# V2_0_2_Contactor_Switch.net
KiCad netlist of a schematic drawn in EasyEDA Pro
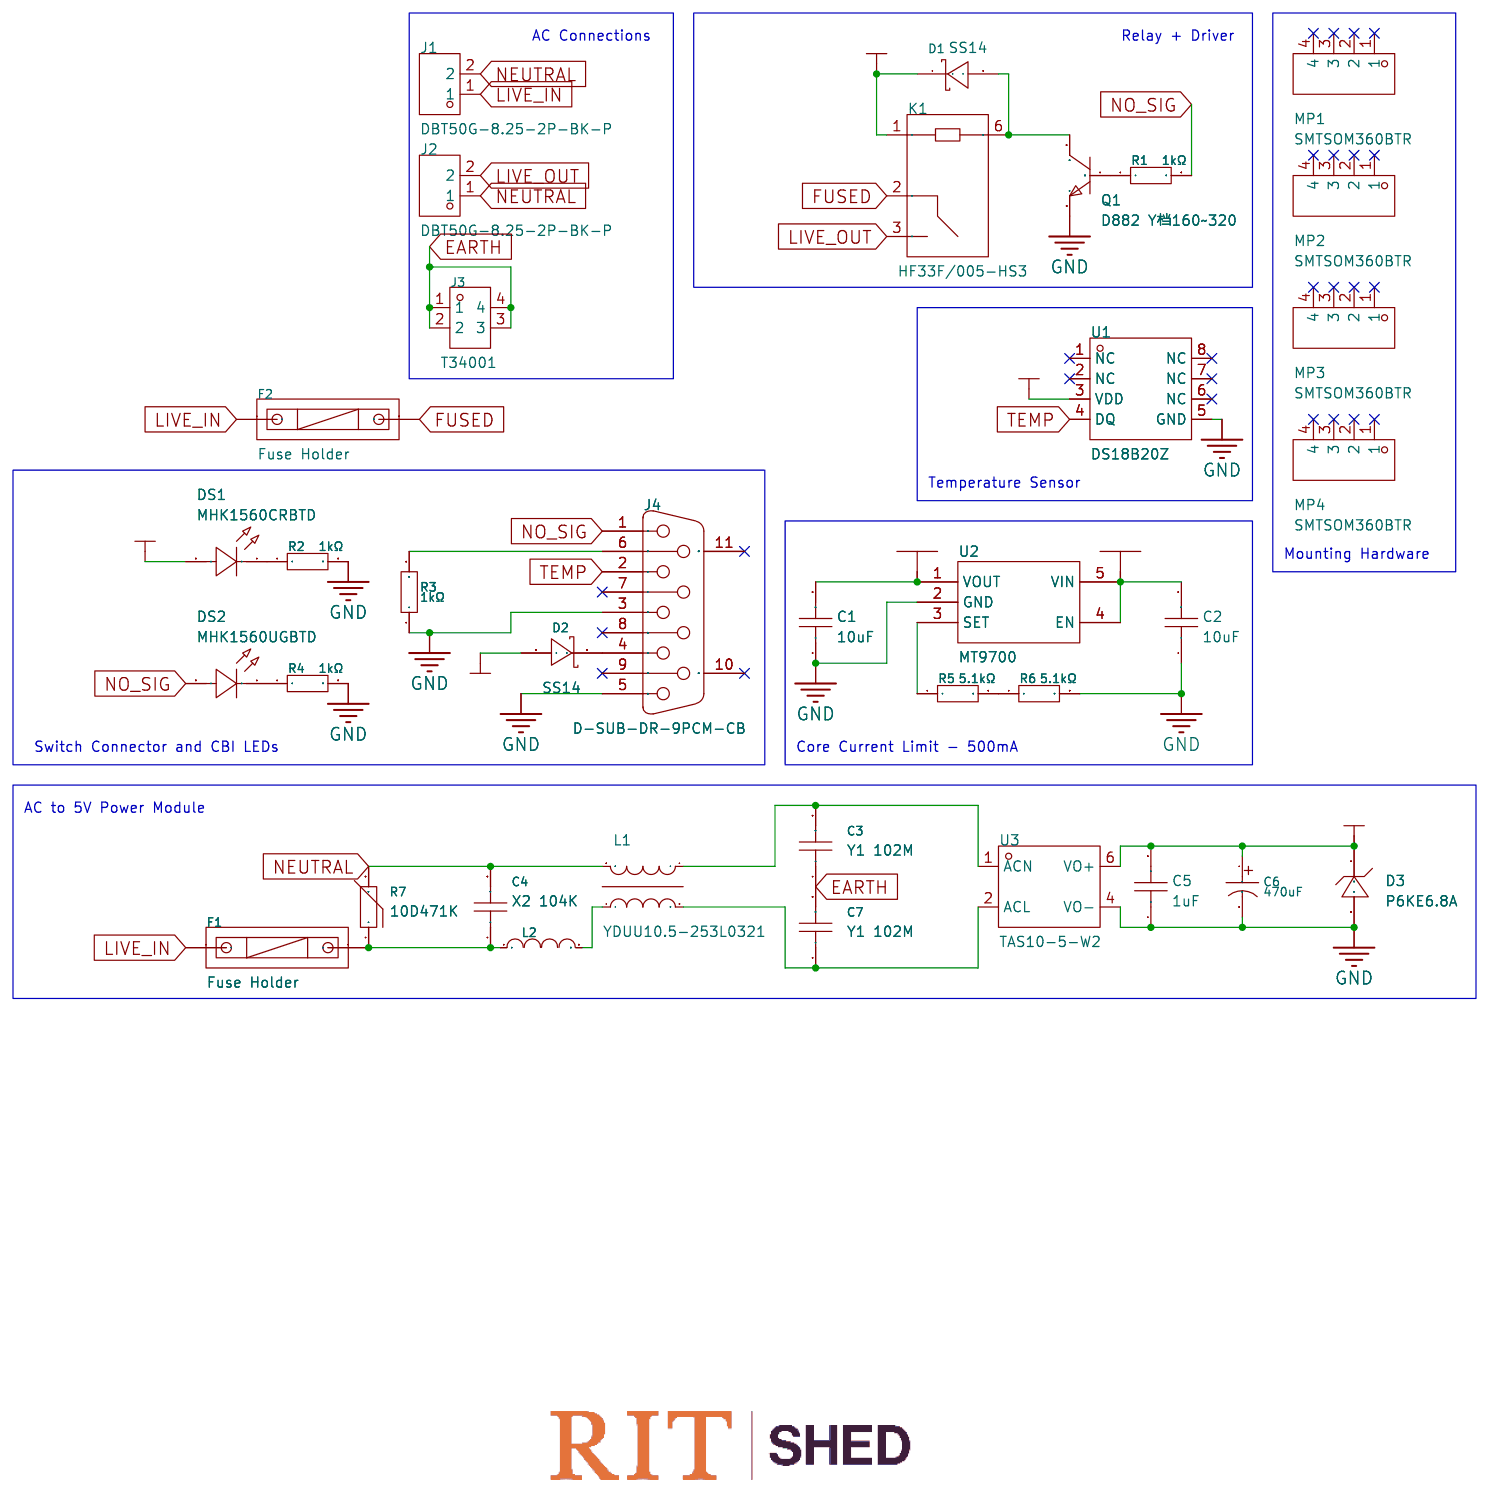
[diagram p0: schematic sheet]

(export (version "E")
  (design (tool "Eeschema 10.0.6"))
  (components
    (comp (ref "C1")
      (value "10uF")
      (footprint "easyedapro:C0603")
      (fields
        (field (name "Manufacturer Part") "CL10A106MA8NRNC")
        (field (name "Manufacturer") "SAMSUNG(三星)")
      )
      (libsource (lib "easyedapro") (part "CL10A106MA8NRNC"))
    )
    (comp (ref "C2")
      (value "10uF")
      (footprint "easyedapro:C0603")
      (fields
        (field (name "Manufacturer Part") "CL10A106MA8NRNC")
        (field (name "Manufacturer") "SAMSUNG(三星)")
      )
      (libsource (lib "easyedapro") (part "CL10A106MA8NRNC"))
    )
    (comp (ref "C3")
      (value "1nF")
      (footprint "easyedapro:CAP-TH_L8.5-W5.0-P10.00-D0.6")
      (fields
        (field (name "Manufacturer Part") "VY1102M31Y5UC63V0")
        (field (name "Manufacturer") "VISHAY(威世)")
      )
      (libsource (lib "easyedapro") (part "VY1102M31Y5UC63V0"))
    )
    (comp (ref "C4")
      (value "100nF")
      (footprint "easyedapro:CAP-TH_L10.0-W5.0-P7.50-D0.6")
      (fields (field (name "Manufacturer Part") "PX104K2C0702") (field (name "Manufacturer") "KYET(科雅)"))
      (libsource (lib "easyedapro") (part "PX104K2C0702"))
    )
    (comp (ref "C5")
      (value "1uF")
      (footprint "easyedapro:C1206")
      (fields
        (field (name "Manufacturer Part") "CL31B105KBHNNNE")
        (field (name "Manufacturer") "SAMSUNG(三星)")
      )
      (libsource (lib "easyedapro") (part "CL31B105KBHNNNE"))
    )
    (comp (ref "C6")
      (value "470uF")
      (footprint "easyedapro:CAP-TH_BD8.0-P3.50-D0.6-FD")
      (fields
        (field (name "Manufacturer Part") "NXA 16V470 8*11.5")
        (field (name "Manufacturer") "SAMYOUNG(韩国三莹)")
      )
      (libsource (lib "easyedapro") (part "NXA-16V470-8*11.5"))
    )
    (comp (ref "C7")
      (value "1nF")
      (footprint "easyedapro:CAP-TH_L8.5-W5.0-P10.00-D0.6")
      (fields
        (field (name "Manufacturer Part") "VY1102M31Y5UC63V0")
        (field (name "Manufacturer") "VISHAY(威世)")
      )
      (libsource (lib "easyedapro") (part "VY1102M31Y5UC63V0"))
    )
    (comp (ref "D1")
      (value "SS14")
      (footprint "easyedapro:SMA_L4.2-W2.6-LS5.3-RD")
      (fields (field (name "Manufacturer") "MDD"))
      (libsource (lib "easyedapro") (part "SS14"))
    )
    (comp (ref "D2")
      (value "SS14")
      (footprint "easyedapro:SMA_L4.2-W2.6-LS5.3-RD")
      (fields (field (name "Manufacturer") "MDD"))
      (libsource (lib "easyedapro") (part "SS14"))
    )
    (comp (ref "D3")
      (value "P6KE6.8A")
      (footprint "easyedapro:DO-15_BD3.1-L6.7-P10.70-D0.9-RD")
      (fields (field (name "Manufacturer") "Littelfuse(美国力特)"))
      (libsource (lib "easyedapro") (part "P6KE6.8A_C409413"))
    )
    (comp (ref "DS1")
      (value "MHK1560CRBTD")
      (footprint "easyedapro:LED-TH_MHK1560UGBTD")
      (fields (field (name "Manufacturer") "MEIHUA(美华)"))
      (libsource (lib "easyedapro") (part "MHK1560CGBTD"))
    )
    (comp (ref "DS2")
      (value "MHK1560UGBTD")
      (footprint "easyedapro:LED-TH_MHK1560UGBTD")
      (fields (field (name "Manufacturer") "MEIHUA(美华)"))
      (libsource (lib "easyedapro") (part "MHK1560UGBTD"))
    )
    (comp (ref "F1")
      (value "Fuse Holder")
      (footprint "easyedapro:FUSE-TH_L24.5-W9.8-P22.5")
      (description "Fuseholder Type:- Fuse Type:- Fuse Size:-")
      (fields (field (name "Manufacturer Part") "保险丝透明座") (field (name "Manufacturer") "xcfuse(旭程)"))
      (libsource (lib "easyedapro") (part "Fuse transparent seat"))
    )
    (comp (ref "F2")
      (value "Fuse Holder")
      (footprint "easyedapro:FUSE-TH_L24.5-W9.8-P22.5")
      (description "Fuseholder Type:- Fuse Type:- Fuse Size:-")
      (fields (field (name "Manufacturer Part") "保险丝透明座") (field (name "Manufacturer") "xcfuse(旭程)"))
      (libsource (lib "easyedapro") (part "Fuse transparent seat"))
    )
    (comp (ref "J1")
      (value "DBT50G-8.25-2P-BK-P")
      (footprint "easyedapro:CONN-TH_DBT50G-8.25-2P")
      (fields (field (name "Manufacturer") "DORABO(地博电气)"))
      (libsource (lib "easyedapro") (part "DBT50G-8.25-2P"))
    )
    (comp (ref "J2")
      (value "DBT50G-8.25-2P-BK-P")
      (footprint "easyedapro:CONN-TH_DBT50G-8.25-2P")
      (fields (field (name "Manufacturer") "DORABO(地博电气)"))
      (libsource (lib "easyedapro") (part "DBT50G-8.25-2P"))
    )
    (comp (ref "J3")
      (value "T34001")
      (footprint "easyedapro:CONN-TH_T34001")
      (fields (field (name "Manufacturer") "XFCN(兴飞)"))
      (libsource (lib "easyedapro") (part "T34001"))
    )
    (comp (ref "J4")
      (value "D-SUB-DR-9PCM-CB")
      (footprint "easyedapro:DB9-TH_ID09S33E4GV00LF")
      (fields (field (name "Manufacturer") "XUNPU(讯普)"))
      (libsource (lib "easyedapro") (part "D-SUB-DR-9PCM-CB"))
    )
    (comp (ref "K1")
      (value "HF33F/005-HS3")
      (footprint "easyedapro:RELAYS-TH_HF33F-XX-HS1-XXX")
      (fields (field (name "Manufacturer") "HF(宏发)"))
      (libsource (lib "easyedapro") (part "HF33F/005-HS3"))
    )
    (comp (ref "L1")
      (value "YDUU10.5-253L0321")
      (footprint "easyedapro:IND-TH_4P-L19.0-W17.0")
      (description "Number of Lines:2 Withstanding Voltage:1.5kV@AC Inductance @ Frequency:25mH@1KHz")
      (fields (field (name "Manufacturer") "YJYCOIN(益嘉源)"))
      (libsource (lib "easyedapro") (part "YDUU10.5-253L0321"))
    )
    (comp (ref "L2")
      (value "560uH")
      (footprint "easyedapro:IND-TH_BD9.0-P5.00-D0.7")
      (description "Inductance: Tolerance:±10% Tolerance:±10% Rated Current: DC Resistance (DCR): Type:工字电感")
      (fields (field (name "Manufacturer Part") "PK0810-561KB") (field (name "Manufacturer") "SXN(顺翔诺)"))
      (libsource (lib "easyedapro") (part "PK0810-561KB"))
    )
    (comp (ref "MP1")
      (value "SMTSOM360BTR")
      (footprint "easyedapro:SMD_BD5.6-D4.1")
      (fields (field (name "Manufacturer") "YIYUAN(怡远)"))
      (libsource (lib "easyedapro") (part "SMTSOM360BTR"))
    )
    (comp (ref "MP2")
      (value "SMTSOM360BTR")
      (footprint "easyedapro:SMD_BD5.6-D4.1")
      (fields (field (name "Manufacturer") "YIYUAN(怡远)"))
      (libsource (lib "easyedapro") (part "SMTSOM360BTR"))
    )
    (comp (ref "MP3")
      (value "SMTSOM360BTR")
      (footprint "easyedapro:SMD_BD5.6-D4.1")
      (fields (field (name "Manufacturer") "YIYUAN(怡远)"))
      (libsource (lib "easyedapro") (part "SMTSOM360BTR"))
    )
    (comp (ref "MP4")
      (value "SMTSOM360BTR")
      (footprint "easyedapro:SMD_BD5.6-D4.1")
      (fields (field (name "Manufacturer") "YIYUAN(怡远)"))
      (libsource (lib "easyedapro") (part "SMTSOM360BTR"))
    )
    (comp (ref "Q1")
      (value "D882 Y档160~320")
      (footprint "easyedapro:SOT-89-3_L4.5-W2.5-P1.50-LS4.2-BR")
      (fields (field (name "Manufacturer") "CJ(江苏长电/长晶)"))
      (libsource (lib "easyedapro") (part "D882_C9634"))
    )
    (comp (ref "R1")
      (value "1kΩ")
      (footprint "easyedapro:R0603")
      (fields
        (field (name "Manufacturer Part") "0603WAF1001T5E")
        (field (name "Manufacturer") "UNI-ROYAL(厚声)")
      )
      (libsource (lib "easyedapro") (part "0603WAF1001T5E"))
    )
    (comp (ref "R2")
      (value "1kΩ")
      (footprint "easyedapro:R0603")
      (fields
        (field (name "Manufacturer Part") "0603WAF1001T5E")
        (field (name "Manufacturer") "UNI-ROYAL(厚声)")
      )
      (libsource (lib "easyedapro") (part "0603WAF1001T5E"))
    )
    (comp (ref "R3")
      (value "1kΩ")
      (footprint "easyedapro:R0603")
      (fields
        (field (name "Manufacturer Part") "0603WAF1001T5E")
        (field (name "Manufacturer") "UNI-ROYAL(厚声)")
      )
      (libsource (lib "easyedapro") (part "0603WAF1001T5E"))
    )
    (comp (ref "R4")
      (value "1kΩ")
      (footprint "easyedapro:R0603")
      (fields
        (field (name "Manufacturer Part") "0603WAF1001T5E")
        (field (name "Manufacturer") "UNI-ROYAL(厚声)")
      )
      (libsource (lib "easyedapro") (part "0603WAF1001T5E"))
    )
    (comp (ref "R5")
      (value "5.1kΩ")
      (footprint "easyedapro:R0603")
      (fields
        (field (name "Manufacturer Part") "0603WAF5101T5E")
        (field (name "Manufacturer") "UNI-ROYAL(厚声)")
      )
      (libsource (lib "easyedapro") (part "0603WAF5101T5E"))
    )
    (comp (ref "R6")
      (value "5.1kΩ")
      (footprint "easyedapro:R0603")
      (fields
        (field (name "Manufacturer Part") "0603WAF5101T5E")
        (field (name "Manufacturer") "UNI-ROYAL(厚声)")
      )
      (libsource (lib "easyedapro") (part "0603WAF5101T5E"))
    )
    (comp (ref "R7")
      (value "10D471K")
      (footprint "easyedapro:RES-TH_L12.5-W6.7-P7.50-D1.2")
      (fields (field (name "Manufacturer") "RUILON(瑞隆源)"))
      (libsource (lib "easyedapro") (part "10D471K-C8760"))
    )
    (comp (ref "U1")
      (value "DS18B20Z")
      (footprint "easyedapro:SOP-8_L4.9-W3.9-P1.27-LS6.0-BL")
      (description "Resolution:±0.4°C Resolution:±0.4°C Supply Voltage:2.5V~5.5V Supply Voltage:2.5V~5.5V")
      (fields (field (name "Manufacturer") "UMW(友台半导体)"))
      (libsource (lib "easyedapro") (part "DS18B20Z"))
    )
    (comp (ref "U2")
      (value "MT9700")
      (footprint "easyedapro:SOT-23-5_L3.0-W1.7-P0.95-LS2.8-BR")
      (fields (field (name "Manufacturer") "西安航天民芯"))
      (libsource (lib "easyedapro") (part "MT9700"))
    )
    (comp (ref "U3")
      (value "TAS10-5-W2")
      (footprint "easyedapro:PWRM-TH_TAS10-XX-W2")
      (fields (field (name "Manufacturer") "TDPOWER(腾达电源)"))
      (libsource (lib "easyedapro") (part "TAS10-5-W2"))
    )
  )
  (nets
    (net (code "1") (name "EARTH") (class "Default")
      (node (ref "C3") (pin "1") (pinfunction "1_1") (pintype "input"))
      (node (ref "C7") (pin "2") (pinfunction "2_2") (pintype "input"))
      (node (ref "J3") (pin "1") (pinfunction "1_1") (pintype "input"))
      (node (ref "J3") (pin "2") (pinfunction "2_2") (pintype "input"))
      (node (ref "J3") (pin "3") (pinfunction "3_3") (pintype "input"))
      (node (ref "J3") (pin "4") (pinfunction "4_4") (pintype "input"))
    )
    (net (code "2") (name "FUSED") (class "Default")
      (node (ref "F2") (pin "2") (pinfunction "2_2") (pintype "input"))
      (node (ref "K1") (pin "2") (pinfunction "2_2") (pintype "input"))
    )
    (net (code "3") (name "GND") (class "Default")
      (node (ref "C1") (pin "1") (pinfunction "1_1") (pintype "input"))
      (node (ref "C2") (pin "1") (pinfunction "1_1") (pintype "input"))
      (node (ref "C5") (pin "1") (pinfunction "1_1") (pintype "unspecified"))
      (node (ref "C6") (pin "2") (pinfunction "2_2") (pintype "input"))
      (node (ref "D3") (pin "2") (pinfunction "A_2") (pintype "input"))
      (node (ref "J4") (pin "3") (pinfunction "3_3") (pintype "input"))
      (node (ref "J4") (pin "5") (pinfunction "5_5") (pintype "input"))
      (node (ref "Q1") (pin "3") (pinfunction "E_3") (pintype "input"))
      (node (ref "R2") (pin "2") (pinfunction "2_2") (pintype "input"))
      (node (ref "R3") (pin "1") (pinfunction "1_1") (pintype "input"))
      (node (ref "R4") (pin "2") (pinfunction "2_2") (pintype "input"))
      (node (ref "R6") (pin "2") (pinfunction "2_2") (pintype "input"))
      (node (ref "U1") (pin "5") (pinfunction "GND_5") (pintype "unspecified"))
      (node (ref "U2") (pin "2") (pinfunction "GND_2") (pintype "input"))
      (node (ref "U3") (pin "4") (pinfunction "VO-_4") (pintype "unspecified"))
    )
    (net (code "4") (name "LIVE_IN") (class "Default")
      (node (ref "F1") (pin "1") (pinfunction "1_1") (pintype "input"))
      (node (ref "F2") (pin "1") (pinfunction "1_1") (pintype "input"))
      (node (ref "J1") (pin "1") (pinfunction "1_1") (pintype "unspecified"))
    )
    (net (code "5") (name "LIVE_OUT") (class "Default")
      (node (ref "J2") (pin "2") (pinfunction "2_2") (pintype "unspecified"))
      (node (ref "K1") (pin "3") (pinfunction "3_3") (pintype "input"))
    )
    (net (code "6") (name "NEUTRAL") (class "Default")
      (node (ref "C4") (pin "2") (pinfunction "2_2") (pintype "input"))
      (node (ref "J1") (pin "2") (pinfunction "2_2") (pintype "unspecified"))
      (node (ref "J2") (pin "1") (pinfunction "1_1") (pintype "unspecified"))
      (node (ref "L1") (pin "3") (pinfunction "3_3") (pintype "unspecified"))
      (node (ref "R7") (pin "2") (pinfunction "2_2") (pintype "input"))
    )
    (net (code "7") (name "NO_SIG") (class "Default")
      (node (ref "DS2") (pin "2") (pinfunction "A_2") (pintype "unspecified"))
      (node (ref "J4") (pin "1") (pinfunction "1_1") (pintype "input"))
      (node (ref "R1") (pin "2") (pinfunction "2_2") (pintype "input"))
    )
    (net (code "8") (name "Net-(C4-Pad1)") (class "Default")
      (node (ref "C4") (pin "1") (pinfunction "1_1") (pintype "input"))
      (node (ref "F1") (pin "2") (pinfunction "2_2") (pintype "input"))
      (node (ref "L2") (pin "1") (pinfunction "1_1") (pintype "input"))
      (node (ref "R7") (pin "1") (pinfunction "1_1") (pintype "input"))
    )
    (net (code "9") (name "Net-(D1-A)") (class "Default")
      (node (ref "D1") (pin "2") (pinfunction "A_2") (pintype "unspecified"))
      (node (ref "K1") (pin "6") (pinfunction "6_6") (pintype "input"))
      (node (ref "Q1") (pin "2") (pinfunction "C_2") (pintype "input"))
    )
    (net (code "10") (name "Net-(D2-K)") (class "Default")
      (node (ref "D2") (pin "1") (pinfunction "K_1") (pintype "unspecified"))
      (node (ref "J4") (pin "4") (pinfunction "4_4") (pintype "input"))
    )
    (net (code "11") (name "Net-(DS1-K)") (class "Default")
      (node (ref "DS1") (pin "1") (pinfunction "K_1") (pintype "unspecified"))
      (node (ref "R2") (pin "1") (pinfunction "1_1") (pintype "input"))
    )
    (net (code "12") (name "Net-(DS2-K)") (class "Default")
      (node (ref "DS2") (pin "1") (pinfunction "K_1") (pintype "unspecified"))
      (node (ref "R4") (pin "1") (pinfunction "1_1") (pintype "input"))
    )
    (net (code "13") (name "Net-(J4-Pad6)") (class "Default")
      (node (ref "J4") (pin "6") (pinfunction "6_6") (pintype "input"))
      (node (ref "R3") (pin "2") (pinfunction "2_2") (pintype "input"))
    )
    (net (code "14") (name "Net-(L1-Pad4)") (class "Default")
      (node (ref "L1") (pin "4") (pinfunction "4_4") (pintype "unspecified"))
      (node (ref "L2") (pin "2") (pinfunction "2_2") (pintype "input"))
    )
    (net (code "15") (name "Net-(Q1-B)") (class "Default")
      (node (ref "Q1") (pin "1") (pinfunction "B_1") (pintype "input"))
      (node (ref "R1") (pin "1") (pinfunction "1_1") (pintype "input"))
    )
    (net (code "16") (name "Net-(R5-Pad2)") (class "Default")
      (node (ref "R5") (pin "2") (pinfunction "2_2") (pintype "input"))
      (node (ref "R6") (pin "1") (pinfunction "1_1") (pintype "input"))
    )
    (net (code "17") (name "Net-(U2-SET)") (class "Default")
      (node (ref "R5") (pin "1") (pinfunction "1_1") (pintype "input"))
      (node (ref "U2") (pin "3") (pinfunction "SET_3") (pintype "input"))
    )
    (net (code "18") (name "Net-(U3-ACL)") (class "Default")
      (node (ref "C7") (pin "1") (pinfunction "1_1") (pintype "input"))
      (node (ref "L1") (pin "2") (pinfunction "2_2") (pintype "unspecified"))
      (node (ref "U3") (pin "2") (pinfunction "ACL_2") (pintype "unspecified"))
    )
    (net (code "19") (name "Net-(U3-ACN)") (class "Default")
      (node (ref "C3") (pin "2") (pinfunction "2_2") (pintype "input"))
      (node (ref "L1") (pin "1") (pinfunction "1_1") (pintype "unspecified"))
      (node (ref "U3") (pin "1") (pinfunction "ACN_1") (pintype "unspecified"))
    )
    (net (code "20") (name "TEMP") (class "Default")
      (node (ref "J4") (pin "2") (pinfunction "2_2") (pintype "input"))
      (node (ref "U1") (pin "4") (pinfunction "DQ_4") (pintype "unspecified"))
    )
    (net (code "21") (name "VRAW") (class "Default")
      (node (ref "C2") (pin "2") (pinfunction "2_2") (pintype "input"))
      (node (ref "C5") (pin "2") (pinfunction "2_2") (pintype "unspecified"))
      (node (ref "C6") (pin "1") (pinfunction "1_1") (pintype "input"))
      (node (ref "D1") (pin "1") (pinfunction "K_1") (pintype "unspecified"))
      (node (ref "D3") (pin "1") (pinfunction "C_1") (pintype "input"))
      (node (ref "K1") (pin "1") (pinfunction "1_1") (pintype "input"))
      (node (ref "U1") (pin "3") (pinfunction "VDD_3") (pintype "unspecified"))
      (node (ref "U2") (pin "4") (pinfunction "EN_4") (pintype "input"))
      (node (ref "U2") (pin "5") (pinfunction "VIN_5") (pintype "input"))
      (node (ref "U3") (pin "6") (pinfunction "VO+_6") (pintype "unspecified"))
    )
    (net (code "22") (name "VSW") (class "Default")
      (node (ref "C1") (pin "2") (pinfunction "2_2") (pintype "input"))
      (node (ref "D2") (pin "2") (pinfunction "A_2") (pintype "unspecified"))
      (node (ref "DS1") (pin "2") (pinfunction "A_2") (pintype "unspecified"))
      (node (ref "U2") (pin "1") (pinfunction "VOUT_1") (pintype "input"))
    )
    (net (code "23") (name "unconnected-(J4-MH1-Pad10)") (class "Default")
      (node (ref "J4") (pin "10") (pinfunction "MH1_10") (pintype "input+no_connect"))
    )
    (net (code "24") (name "unconnected-(J4-MH2-Pad11)") (class "Default")
      (node (ref "J4") (pin "11") (pinfunction "MH2_11") (pintype "input+no_connect"))
    )
    (net (code "25") (name "unconnected-(J4-Pad7)") (class "Default")
      (node (ref "J4") (pin "7") (pinfunction "7_7") (pintype "input+no_connect"))
    )
    (net (code "26") (name "unconnected-(J4-Pad8)") (class "Default")
      (node (ref "J4") (pin "8") (pinfunction "8_8") (pintype "input+no_connect"))
    )
    (net (code "27") (name "unconnected-(J4-Pad9)") (class "Default")
      (node (ref "J4") (pin "9") (pinfunction "9_9") (pintype "input+no_connect"))
    )
    (net (code "28") (name "unconnected-(MP1-Pad1)") (class "Default")
      (node (ref "MP1") (pin "1") (pinfunction "1_1") (pintype "unspecified+no_connect"))
    )
    (net (code "29") (name "unconnected-(MP1-Pad2)") (class "Default")
      (node (ref "MP1") (pin "2") (pinfunction "2_2") (pintype "unspecified+no_connect"))
    )
    (net (code "30") (name "unconnected-(MP1-Pad3)") (class "Default")
      (node (ref "MP1") (pin "3") (pinfunction "3_3") (pintype "unspecified+no_connect"))
    )
    (net (code "31") (name "unconnected-(MP1-Pad4)") (class "Default")
      (node (ref "MP1") (pin "4") (pinfunction "4_4") (pintype "unspecified+no_connect"))
    )
    (net (code "32") (name "unconnected-(MP2-Pad1)") (class "Default")
      (node (ref "MP2") (pin "1") (pinfunction "1_1") (pintype "unspecified+no_connect"))
    )
    (net (code "33") (name "unconnected-(MP2-Pad2)") (class "Default")
      (node (ref "MP2") (pin "2") (pinfunction "2_2") (pintype "unspecified+no_connect"))
    )
    (net (code "34") (name "unconnected-(MP2-Pad3)") (class "Default")
      (node (ref "MP2") (pin "3") (pinfunction "3_3") (pintype "unspecified+no_connect"))
    )
    (net (code "35") (name "unconnected-(MP2-Pad4)") (class "Default")
      (node (ref "MP2") (pin "4") (pinfunction "4_4") (pintype "unspecified+no_connect"))
    )
    (net (code "36") (name "unconnected-(MP3-Pad1)") (class "Default")
      (node (ref "MP3") (pin "1") (pinfunction "1_1") (pintype "unspecified+no_connect"))
    )
    (net (code "37") (name "unconnected-(MP3-Pad2)") (class "Default")
      (node (ref "MP3") (pin "2") (pinfunction "2_2") (pintype "unspecified+no_connect"))
    )
    (net (code "38") (name "unconnected-(MP3-Pad3)") (class "Default")
      (node (ref "MP3") (pin "3") (pinfunction "3_3") (pintype "unspecified+no_connect"))
    )
    (net (code "39") (name "unconnected-(MP3-Pad4)") (class "Default")
      (node (ref "MP3") (pin "4") (pinfunction "4_4") (pintype "unspecified+no_connect"))
    )
    (net (code "40") (name "unconnected-(MP4-Pad1)") (class "Default")
      (node (ref "MP4") (pin "1") (pinfunction "1_1") (pintype "unspecified+no_connect"))
    )
    (net (code "41") (name "unconnected-(MP4-Pad2)") (class "Default")
      (node (ref "MP4") (pin "2") (pinfunction "2_2") (pintype "unspecified+no_connect"))
    )
    (net (code "42") (name "unconnected-(MP4-Pad3)") (class "Default")
      (node (ref "MP4") (pin "3") (pinfunction "3_3") (pintype "unspecified+no_connect"))
    )
    (net (code "43") (name "unconnected-(MP4-Pad4)") (class "Default")
      (node (ref "MP4") (pin "4") (pinfunction "4_4") (pintype "unspecified+no_connect"))
    )
    (net (code "44") (name "unconnected-(U1-NC-Pad1)") (class "Default")
      (node (ref "U1") (pin "1") (pinfunction "NC_1") (pintype "unspecified+no_connect"))
    )
    (net (code "45") (name "unconnected-(U1-NC-Pad2)") (class "Default")
      (node (ref "U1") (pin "2") (pinfunction "NC_2") (pintype "unspecified+no_connect"))
    )
    (net (code "46") (name "unconnected-(U1-NC-Pad6)") (class "Default")
      (node (ref "U1") (pin "6") (pinfunction "NC_6") (pintype "unspecified+no_connect"))
    )
    (net (code "47") (name "unconnected-(U1-NC-Pad7)") (class "Default")
      (node (ref "U1") (pin "7") (pinfunction "NC_7") (pintype "unspecified+no_connect"))
    )
    (net (code "48") (name "unconnected-(U1-NC-Pad8)") (class "Default")
      (node (ref "U1") (pin "8") (pinfunction "NC_8") (pintype "unspecified+no_connect"))
    )
  )
)
